# link_board.net
KiCad netlist of a schematic drawn in EasyEDA Pro
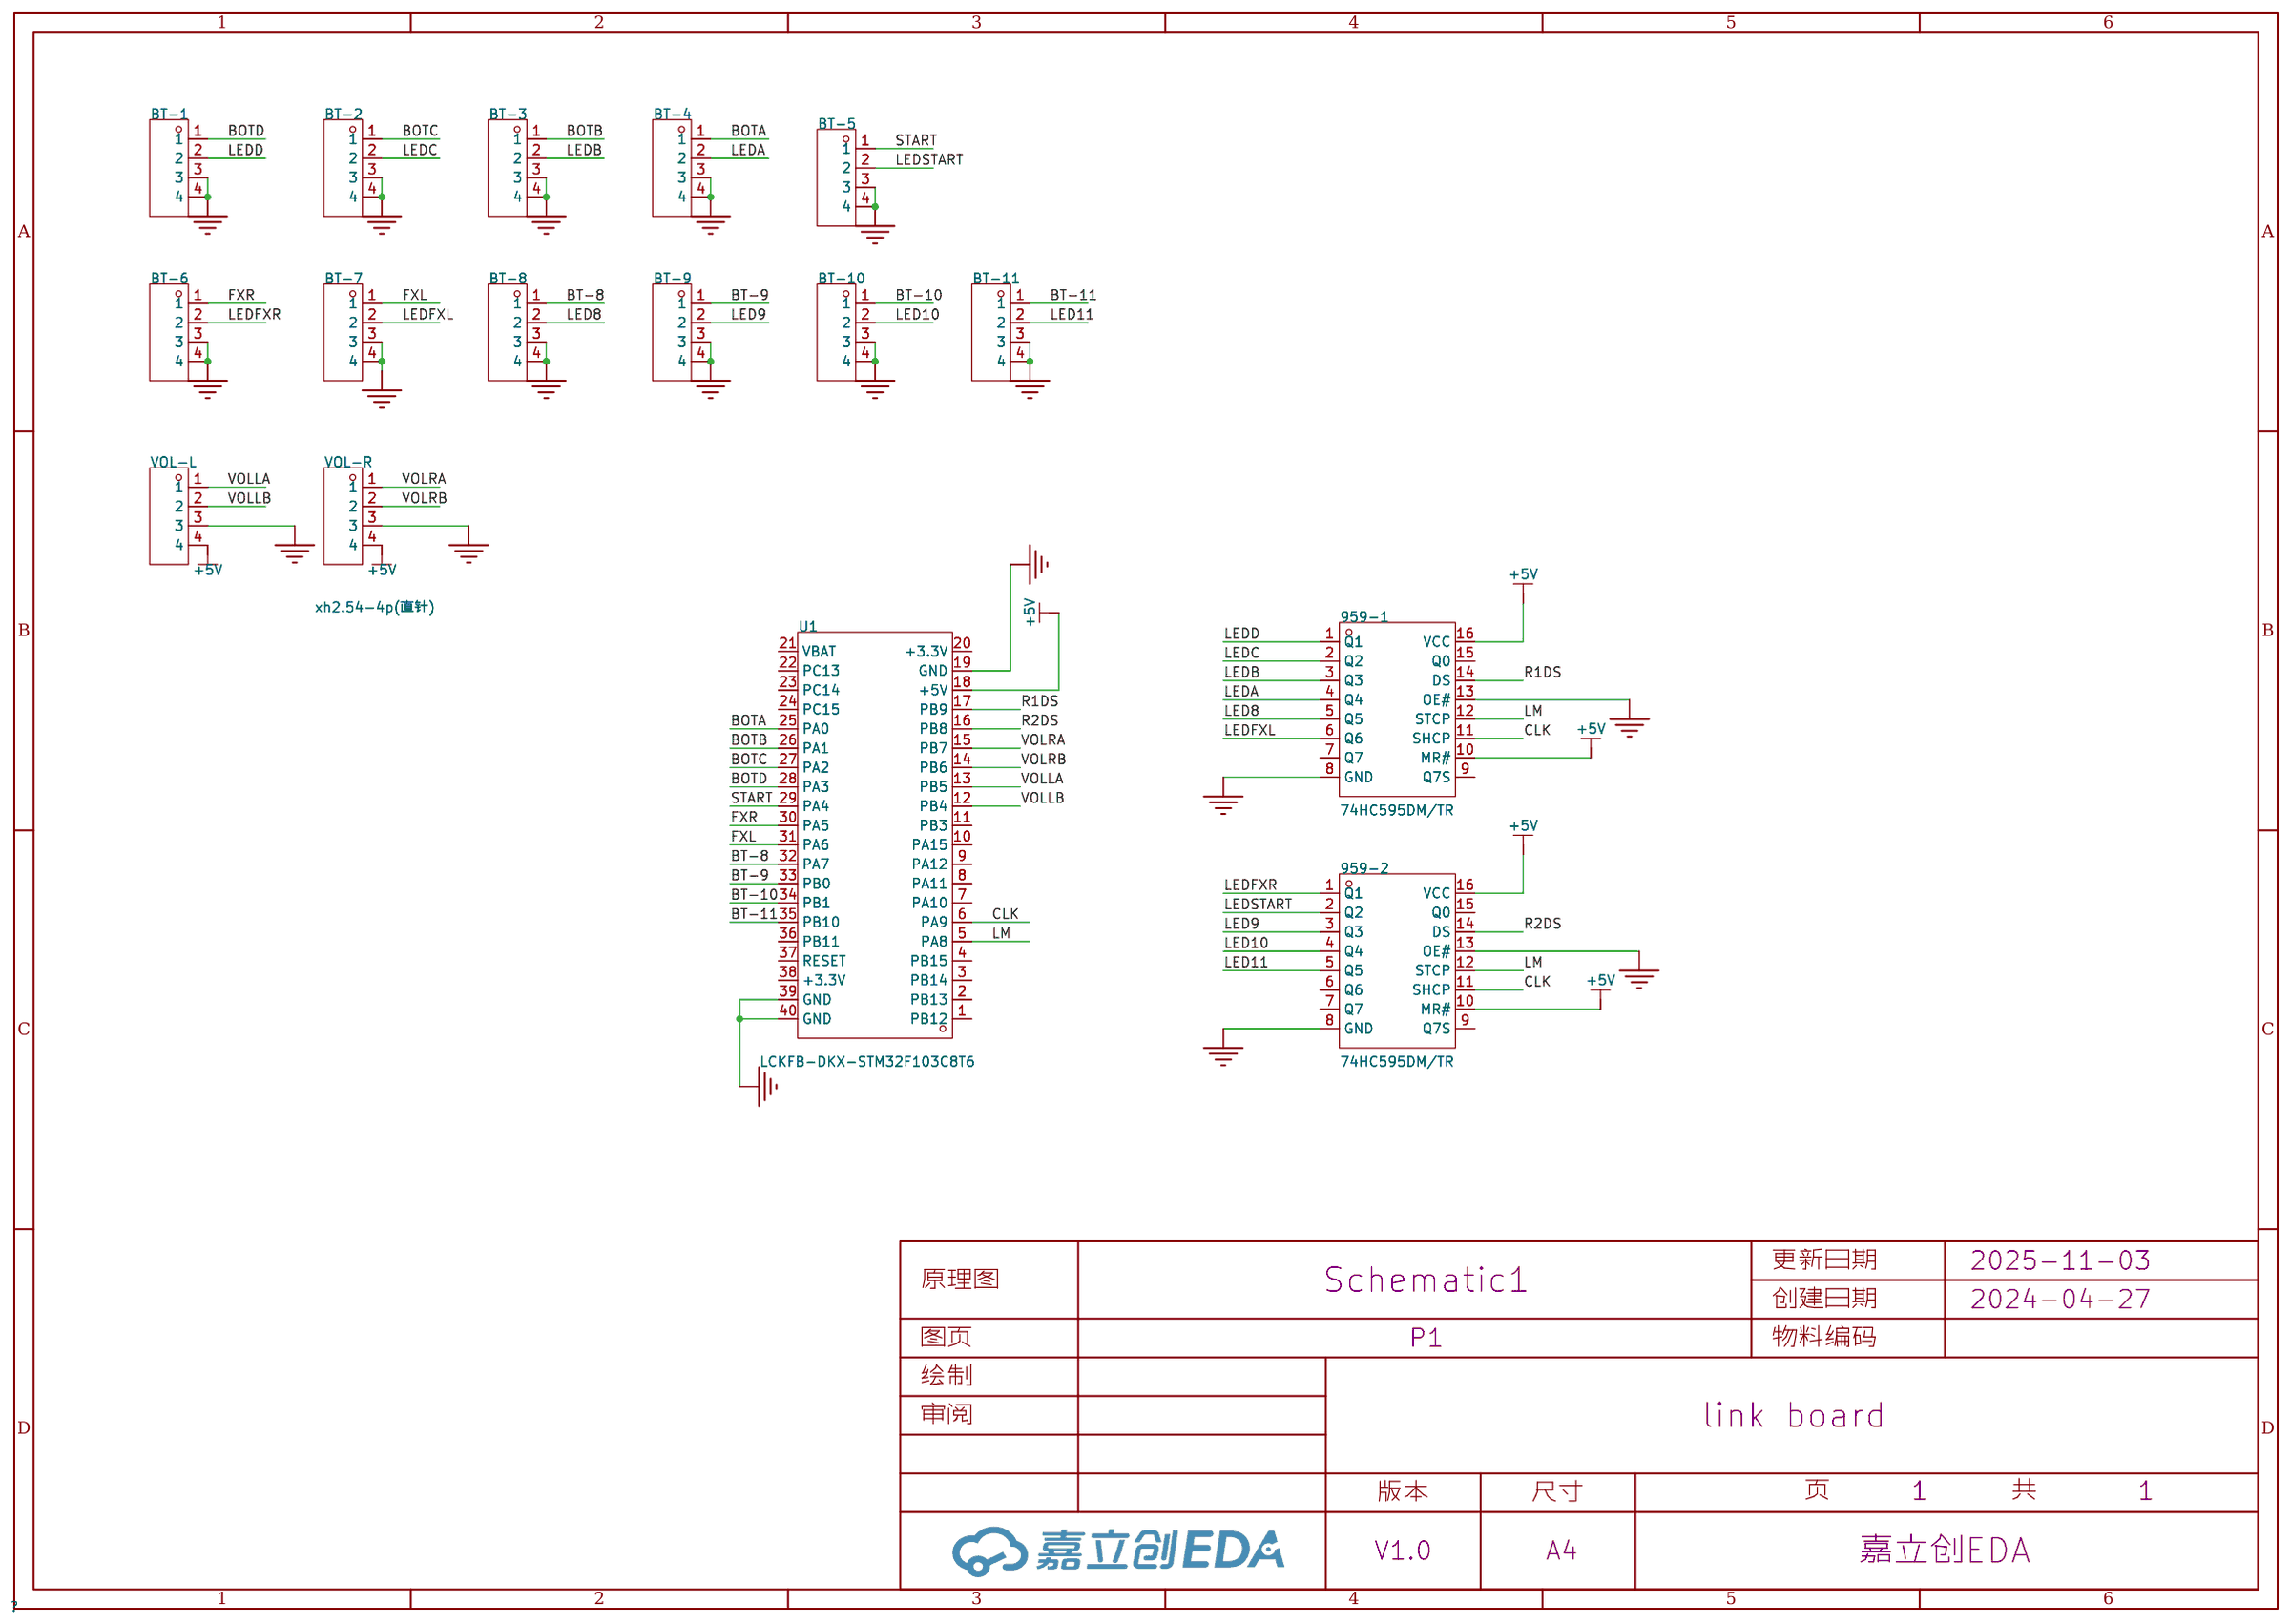
[diagram p0: schematic sheet]

(export (version "E")
  (design (tool "Eeschema 10.0.6"))
  (components
    (comp (ref "959-1")
      (value "74HC595DM/TR")
      (footprint "easyedapro:SOP-16_L9.9-W3.9-P1.27-LS6.0-BL")
      (description "每个元件位数:8;")
      (fields (field (name "Manufacturer") "HGSEMI(华冠)"))
      (libsource (lib "easyedapro") (part "74HC595DM/TR"))
    )
    (comp (ref "959-2")
      (value "74HC595DM/TR")
      (footprint "easyedapro:SOP-16_L9.9-W3.9-P1.27-LS6.0-BL")
      (description "每个元件位数:8;")
      (fields (field (name "Manufacturer") "HGSEMI(华冠)"))
      (libsource (lib "easyedapro") (part "74HC595DM/TR"))
    )
    (comp (ref "BT-1")
      (value "xh2.54-4p(直针)")
      (footprint "easyedapro:CONN-TH_4P-P2.50-XH2.54-4P")
      (libsource (lib "easyedapro") (part "XH2.54-4P(直针)"))
    )
    (comp (ref "BT-2")
      (value "xh2.54-4p(直针)")
      (footprint "easyedapro:CONN-TH_4P-P2.50-XH2.54-4P")
      (libsource (lib "easyedapro") (part "XH2.54-4P(直针)"))
    )
    (comp (ref "BT-3")
      (value "xh2.54-4p(直针)")
      (footprint "easyedapro:CONN-TH_4P-P2.50-XH2.54-4P")
      (libsource (lib "easyedapro") (part "XH2.54-4P(直针)"))
    )
    (comp (ref "BT-4")
      (value "xh2.54-4p(直针)")
      (footprint "easyedapro:CONN-TH_4P-P2.50-XH2.54-4P")
      (libsource (lib "easyedapro") (part "XH2.54-4P(直针)"))
    )
    (comp (ref "BT-5")
      (value "xh2.54-4p(直针)")
      (footprint "easyedapro:CONN-TH_4P-P2.50-XH2.54-4P")
      (libsource (lib "easyedapro") (part "XH2.54-4P(直针)"))
    )
    (comp (ref "BT-6")
      (value "xh2.54-4p(直针)")
      (footprint "easyedapro:CONN-TH_4P-P2.50-XH2.54-4P")
      (libsource (lib "easyedapro") (part "XH2.54-4P(直针)"))
    )
    (comp (ref "BT-7")
      (value "xh2.54-4p(直针)")
      (footprint "easyedapro:CONN-TH_4P-P2.50-XH2.54-4P")
      (libsource (lib "easyedapro") (part "XH2.54-4P(直针)"))
    )
    (comp (ref "BT-8")
      (value "xh2.54-4p(直针)")
      (footprint "easyedapro:CONN-TH_4P-P2.50-XH2.54-4P")
      (libsource (lib "easyedapro") (part "XH2.54-4P(直针)"))
    )
    (comp (ref "BT-9")
      (value "xh2.54-4p(直针)")
      (footprint "easyedapro:CONN-TH_4P-P2.50-XH2.54-4P")
      (libsource (lib "easyedapro") (part "XH2.54-4P(直针)"))
    )
    (comp (ref "BT-10")
      (value "xh2.54-4p(直针)")
      (footprint "easyedapro:CONN-TH_4P-P2.50-XH2.54-4P")
      (libsource (lib "easyedapro") (part "XH2.54-4P(直针)"))
    )
    (comp (ref "BT-11")
      (value "xh2.54-4p(直针)")
      (footprint "easyedapro:CONN-TH_4P-P2.50-XH2.54-4P")
      (libsource (lib "easyedapro") (part "XH2.54-4P(直针)"))
    )
    (comp (ref "U1")
      (value "LCKFB-DKX-STM32F103C8T6")
      (footprint "easyedapro:CONN-TH_L53.3-W22.9_STM32F103C8T6-CARD")
      (fields (field (name "Manufacturer") "立创开发板"))
      (libsource (lib "easyedapro") (part "LCKFB-DKX-STM32F103C8T6"))
    )
    (comp (ref "VOL-L")
      (value "xh2.54-4p(直针)")
      (footprint "easyedapro:CONN-TH_4P-P2.50-XH2.54-4P")
      (libsource (lib "easyedapro") (part "XH2.54-4P(直针)"))
    )
    (comp (ref "VOL-R")
      (value "xh2.54-4p(直针)")
      (footprint "easyedapro:CONN-TH_4P-P2.50-XH2.54-4P")
      (libsource (lib "easyedapro") (part "XH2.54-4P(直针)"))
    )
  )
  (nets
    (net (code "1") (name "+5V") (class "Default")
      (node (ref "959-1") (pin "10") (pinfunction "MR#_10") (pintype "unspecified"))
      (node (ref "959-1") (pin "16") (pinfunction "VCC_16") (pintype "unspecified"))
      (node (ref "959-2") (pin "10") (pinfunction "MR#_10") (pintype "unspecified"))
      (node (ref "959-2") (pin "16") (pinfunction "VCC_16") (pintype "unspecified"))
      (node (ref "U1") (pin "18") (pinfunction "+5V_18") (pintype "unspecified"))
      (node (ref "VOL-L") (pin "4") (pinfunction "4_4") (pintype "unspecified"))
      (node (ref "VOL-R") (pin "4") (pinfunction "4_4") (pintype "unspecified"))
    )
    (net (code "2") (name "/BOTA") (class "Default")
      (node (ref "BT-4") (pin "1") (pinfunction "1_1") (pintype "unspecified"))
      (node (ref "U1") (pin "25") (pinfunction "PA0_25") (pintype "unspecified"))
    )
    (net (code "3") (name "/BOTB") (class "Default")
      (node (ref "BT-3") (pin "1") (pinfunction "1_1") (pintype "unspecified"))
      (node (ref "U1") (pin "26") (pinfunction "PA1_26") (pintype "unspecified"))
    )
    (net (code "4") (name "/BOTC") (class "Default")
      (node (ref "BT-2") (pin "1") (pinfunction "1_1") (pintype "unspecified"))
      (node (ref "U1") (pin "27") (pinfunction "PA2_27") (pintype "unspecified"))
    )
    (net (code "5") (name "/BOTD") (class "Default")
      (node (ref "BT-1") (pin "1") (pinfunction "1_1") (pintype "unspecified"))
      (node (ref "U1") (pin "28") (pinfunction "PA3_28") (pintype "unspecified"))
    )
    (net (code "6") (name "/BT-8") (class "Default")
      (node (ref "BT-8") (pin "1") (pinfunction "1_1") (pintype "unspecified"))
      (node (ref "U1") (pin "32") (pinfunction "PA7_32") (pintype "unspecified"))
    )
    (net (code "7") (name "/BT-9") (class "Default")
      (node (ref "BT-9") (pin "1") (pinfunction "1_1") (pintype "unspecified"))
      (node (ref "U1") (pin "33") (pinfunction "PB0_33") (pintype "unspecified"))
    )
    (net (code "8") (name "/BT-10") (class "Default")
      (node (ref "BT-10") (pin "1") (pinfunction "1_1") (pintype "unspecified"))
      (node (ref "U1") (pin "34") (pinfunction "PB1_34") (pintype "unspecified"))
    )
    (net (code "9") (name "/BT-11") (class "Default")
      (node (ref "BT-11") (pin "1") (pinfunction "1_1") (pintype "unspecified"))
      (node (ref "U1") (pin "35") (pinfunction "PB10_35") (pintype "unspecified"))
    )
    (net (code "10") (name "/CLK") (class "Default")
      (node (ref "959-1") (pin "11") (pinfunction "SHCP_11") (pintype "unspecified"))
      (node (ref "959-2") (pin "11") (pinfunction "SHCP_11") (pintype "unspecified"))
      (node (ref "U1") (pin "6") (pinfunction "PA9_6") (pintype "unspecified"))
    )
    (net (code "11") (name "/FXL") (class "Default")
      (node (ref "BT-7") (pin "1") (pinfunction "1_1") (pintype "unspecified"))
      (node (ref "U1") (pin "31") (pinfunction "PA6_31") (pintype "unspecified"))
    )
    (net (code "12") (name "/FXR") (class "Default")
      (node (ref "BT-6") (pin "1") (pinfunction "1_1") (pintype "unspecified"))
      (node (ref "U1") (pin "30") (pinfunction "PA5_30") (pintype "unspecified"))
    )
    (net (code "13") (name "/LED8") (class "Default")
      (node (ref "959-1") (pin "5") (pinfunction "Q5_5") (pintype "unspecified"))
      (node (ref "BT-8") (pin "2") (pinfunction "2_2") (pintype "unspecified"))
    )
    (net (code "14") (name "/LED9") (class "Default")
      (node (ref "959-2") (pin "3") (pinfunction "Q3_3") (pintype "unspecified"))
      (node (ref "BT-9") (pin "2") (pinfunction "2_2") (pintype "unspecified"))
    )
    (net (code "15") (name "/LED10") (class "Default")
      (node (ref "959-2") (pin "4") (pinfunction "Q4_4") (pintype "unspecified"))
      (node (ref "BT-10") (pin "2") (pinfunction "2_2") (pintype "unspecified"))
    )
    (net (code "16") (name "/LED11") (class "Default")
      (node (ref "959-2") (pin "5") (pinfunction "Q5_5") (pintype "unspecified"))
      (node (ref "BT-11") (pin "2") (pinfunction "2_2") (pintype "unspecified"))
    )
    (net (code "17") (name "/LEDA") (class "Default")
      (node (ref "959-1") (pin "4") (pinfunction "Q4_4") (pintype "unspecified"))
      (node (ref "BT-4") (pin "2") (pinfunction "2_2") (pintype "unspecified"))
    )
    (net (code "18") (name "/LEDB") (class "Default")
      (node (ref "959-1") (pin "3") (pinfunction "Q3_3") (pintype "unspecified"))
      (node (ref "BT-3") (pin "2") (pinfunction "2_2") (pintype "unspecified"))
    )
    (net (code "19") (name "/LEDC") (class "Default")
      (node (ref "959-1") (pin "2") (pinfunction "Q2_2") (pintype "unspecified"))
      (node (ref "BT-2") (pin "2") (pinfunction "2_2") (pintype "unspecified"))
    )
    (net (code "20") (name "/LEDD") (class "Default")
      (node (ref "959-1") (pin "1") (pinfunction "Q1_1") (pintype "unspecified"))
      (node (ref "BT-1") (pin "2") (pinfunction "2_2") (pintype "unspecified"))
    )
    (net (code "21") (name "/LEDFXL") (class "Default")
      (node (ref "959-1") (pin "6") (pinfunction "Q6_6") (pintype "unspecified"))
      (node (ref "BT-7") (pin "2") (pinfunction "2_2") (pintype "unspecified"))
    )
    (net (code "22") (name "/LEDFXR") (class "Default")
      (node (ref "959-2") (pin "1") (pinfunction "Q1_1") (pintype "unspecified"))
      (node (ref "BT-6") (pin "2") (pinfunction "2_2") (pintype "unspecified"))
    )
    (net (code "23") (name "/LEDSTART") (class "Default")
      (node (ref "959-2") (pin "2") (pinfunction "Q2_2") (pintype "unspecified"))
      (node (ref "BT-5") (pin "2") (pinfunction "2_2") (pintype "unspecified"))
    )
    (net (code "24") (name "/LM") (class "Default")
      (node (ref "959-1") (pin "12") (pinfunction "STCP_12") (pintype "unspecified"))
      (node (ref "959-2") (pin "12") (pinfunction "STCP_12") (pintype "unspecified"))
      (node (ref "U1") (pin "5") (pinfunction "PA8_5") (pintype "unspecified"))
    )
    (net (code "25") (name "/R1DS") (class "Default")
      (node (ref "959-1") (pin "14") (pinfunction "DS_14") (pintype "unspecified"))
      (node (ref "U1") (pin "17") (pinfunction "PB9_17") (pintype "unspecified"))
    )
    (net (code "26") (name "/R2DS") (class "Default")
      (node (ref "959-2") (pin "14") (pinfunction "DS_14") (pintype "unspecified"))
      (node (ref "U1") (pin "16") (pinfunction "PB8_16") (pintype "unspecified"))
    )
    (net (code "27") (name "/START") (class "Default")
      (node (ref "BT-5") (pin "1") (pinfunction "1_1") (pintype "unspecified"))
      (node (ref "U1") (pin "29") (pinfunction "PA4_29") (pintype "unspecified"))
    )
    (net (code "28") (name "/VOLLA") (class "Default")
      (node (ref "U1") (pin "13") (pinfunction "PB5_13") (pintype "unspecified"))
      (node (ref "VOL-L") (pin "1") (pinfunction "1_1") (pintype "unspecified"))
    )
    (net (code "29") (name "/VOLLB") (class "Default")
      (node (ref "U1") (pin "12") (pinfunction "PB4_12") (pintype "unspecified"))
      (node (ref "VOL-L") (pin "2") (pinfunction "2_2") (pintype "unspecified"))
    )
    (net (code "30") (name "/VOLRA") (class "Default")
      (node (ref "U1") (pin "15") (pinfunction "PB7_15") (pintype "unspecified"))
      (node (ref "VOL-R") (pin "1") (pinfunction "1_1") (pintype "unspecified"))
    )
    (net (code "31") (name "/VOLRB") (class "Default")
      (node (ref "U1") (pin "14") (pinfunction "PB6_14") (pintype "unspecified"))
      (node (ref "VOL-R") (pin "2") (pinfunction "2_2") (pintype "unspecified"))
    )
    (net (code "32") (name "GND") (class "Default")
      (node (ref "959-1") (pin "13") (pinfunction "OE#_13") (pintype "unspecified"))
      (node (ref "959-1") (pin "8") (pinfunction "GND_8") (pintype "unspecified"))
      (node (ref "959-2") (pin "13") (pinfunction "OE#_13") (pintype "unspecified"))
      (node (ref "959-2") (pin "8") (pinfunction "GND_8") (pintype "unspecified"))
      (node (ref "BT-1") (pin "3") (pinfunction "3_3") (pintype "unspecified"))
      (node (ref "BT-1") (pin "4") (pinfunction "4_4") (pintype "unspecified"))
      (node (ref "BT-10") (pin "3") (pinfunction "3_3") (pintype "unspecified"))
      (node (ref "BT-10") (pin "4") (pinfunction "4_4") (pintype "unspecified"))
      (node (ref "BT-11") (pin "3") (pinfunction "3_3") (pintype "unspecified"))
      (node (ref "BT-11") (pin "4") (pinfunction "4_4") (pintype "unspecified"))
      (node (ref "BT-2") (pin "3") (pinfunction "3_3") (pintype "unspecified"))
      (node (ref "BT-2") (pin "4") (pinfunction "4_4") (pintype "unspecified"))
      (node (ref "BT-3") (pin "3") (pinfunction "3_3") (pintype "unspecified"))
      (node (ref "BT-3") (pin "4") (pinfunction "4_4") (pintype "unspecified"))
      (node (ref "BT-4") (pin "3") (pinfunction "3_3") (pintype "unspecified"))
      (node (ref "BT-4") (pin "4") (pinfunction "4_4") (pintype "unspecified"))
      (node (ref "BT-5") (pin "3") (pinfunction "3_3") (pintype "unspecified"))
      (node (ref "BT-5") (pin "4") (pinfunction "4_4") (pintype "unspecified"))
      (node (ref "BT-6") (pin "3") (pinfunction "3_3") (pintype "unspecified"))
      (node (ref "BT-6") (pin "4") (pinfunction "4_4") (pintype "unspecified"))
      (node (ref "BT-7") (pin "3") (pinfunction "3_3") (pintype "unspecified"))
      (node (ref "BT-7") (pin "4") (pinfunction "4_4") (pintype "unspecified"))
      (node (ref "BT-8") (pin "3") (pinfunction "3_3") (pintype "unspecified"))
      (node (ref "BT-8") (pin "4") (pinfunction "4_4") (pintype "unspecified"))
      (node (ref "BT-9") (pin "3") (pinfunction "3_3") (pintype "unspecified"))
      (node (ref "BT-9") (pin "4") (pinfunction "4_4") (pintype "unspecified"))
      (node (ref "U1") (pin "19") (pinfunction "GND_19") (pintype "unspecified"))
      (node (ref "U1") (pin "39") (pinfunction "GND_39") (pintype "unspecified"))
      (node (ref "U1") (pin "40") (pinfunction "GND_40") (pintype "unspecified"))
      (node (ref "VOL-L") (pin "3") (pinfunction "3_3") (pintype "unspecified"))
      (node (ref "VOL-R") (pin "3") (pinfunction "3_3") (pintype "unspecified"))
    )
    (net (code "33") (name "unconnected-(959-1-Q0-Pad15)") (class "Default")
      (node (ref "959-1") (pin "15") (pinfunction "Q0_15") (pintype "unspecified"))
    )
    (net (code "34") (name "unconnected-(959-1-Q7-Pad7)") (class "Default")
      (node (ref "959-1") (pin "7") (pinfunction "Q7_7") (pintype "unspecified"))
    )
    (net (code "35") (name "unconnected-(959-1-Q7S-Pad9)") (class "Default")
      (node (ref "959-1") (pin "9") (pinfunction "Q7S_9") (pintype "unspecified"))
    )
    (net (code "36") (name "unconnected-(959-2-Q0-Pad15)") (class "Default")
      (node (ref "959-2") (pin "15") (pinfunction "Q0_15") (pintype "unspecified"))
    )
    (net (code "37") (name "unconnected-(959-2-Q6-Pad6)") (class "Default")
      (node (ref "959-2") (pin "6") (pinfunction "Q6_6") (pintype "unspecified"))
    )
    (net (code "38") (name "unconnected-(959-2-Q7-Pad7)") (class "Default")
      (node (ref "959-2") (pin "7") (pinfunction "Q7_7") (pintype "unspecified"))
    )
    (net (code "39") (name "unconnected-(959-2-Q7S-Pad9)") (class "Default")
      (node (ref "959-2") (pin "9") (pinfunction "Q7S_9") (pintype "unspecified"))
    )
    (net (code "40") (name "unconnected-(U1-+3.3V-Pad20)") (class "Default")
      (node (ref "U1") (pin "20") (pinfunction "+3.3V_20") (pintype "unspecified"))
    )
    (net (code "41") (name "unconnected-(U1-+3.3V-Pad38)") (class "Default")
      (node (ref "U1") (pin "38") (pinfunction "+3.3V_38") (pintype "unspecified"))
    )
    (net (code "42") (name "unconnected-(U1-PA10-Pad7)") (class "Default")
      (node (ref "U1") (pin "7") (pinfunction "PA10_7") (pintype "unspecified"))
    )
    (net (code "43") (name "unconnected-(U1-PA11-Pad8)") (class "Default")
      (node (ref "U1") (pin "8") (pinfunction "PA11_8") (pintype "unspecified"))
    )
    (net (code "44") (name "unconnected-(U1-PA12-Pad9)") (class "Default")
      (node (ref "U1") (pin "9") (pinfunction "PA12_9") (pintype "unspecified"))
    )
    (net (code "45") (name "unconnected-(U1-PA15-Pad10)") (class "Default")
      (node (ref "U1") (pin "10") (pinfunction "PA15_10") (pintype "unspecified"))
    )
    (net (code "46") (name "unconnected-(U1-PB3-Pad11)") (class "Default")
      (node (ref "U1") (pin "11") (pinfunction "PB3_11") (pintype "unspecified"))
    )
    (net (code "47") (name "unconnected-(U1-PB11-Pad36)") (class "Default")
      (node (ref "U1") (pin "36") (pinfunction "PB11_36") (pintype "unspecified"))
    )
    (net (code "48") (name "unconnected-(U1-PB12-Pad1)") (class "Default")
      (node (ref "U1") (pin "1") (pinfunction "PB12_1") (pintype "unspecified"))
    )
    (net (code "49") (name "unconnected-(U1-PB13-Pad2)") (class "Default")
      (node (ref "U1") (pin "2") (pinfunction "PB13_2") (pintype "unspecified"))
    )
    (net (code "50") (name "unconnected-(U1-PB14-Pad3)") (class "Default")
      (node (ref "U1") (pin "3") (pinfunction "PB14_3") (pintype "unspecified"))
    )
    (net (code "51") (name "unconnected-(U1-PB15-Pad4)") (class "Default")
      (node (ref "U1") (pin "4") (pinfunction "PB15_4") (pintype "unspecified"))
    )
    (net (code "52") (name "unconnected-(U1-PC13-Pad22)") (class "Default")
      (node (ref "U1") (pin "22") (pinfunction "PC13_22") (pintype "unspecified"))
    )
    (net (code "53") (name "unconnected-(U1-PC14-Pad23)") (class "Default")
      (node (ref "U1") (pin "23") (pinfunction "PC14_23") (pintype "unspecified"))
    )
    (net (code "54") (name "unconnected-(U1-PC15-Pad24)") (class "Default")
      (node (ref "U1") (pin "24") (pinfunction "PC15_24") (pintype "unspecified"))
    )
    (net (code "55") (name "unconnected-(U1-RESET-Pad37)") (class "Default")
      (node (ref "U1") (pin "37") (pinfunction "RESET_37") (pintype "unspecified"))
    )
    (net (code "56") (name "unconnected-(U1-VBAT-Pad21)") (class "Default")
      (node (ref "U1") (pin "21") (pinfunction "VBAT_21") (pintype "unspecified"))
    )
  )
)
